# MCU.net
KiCad netlist of a schematic drawn in Altium Designer
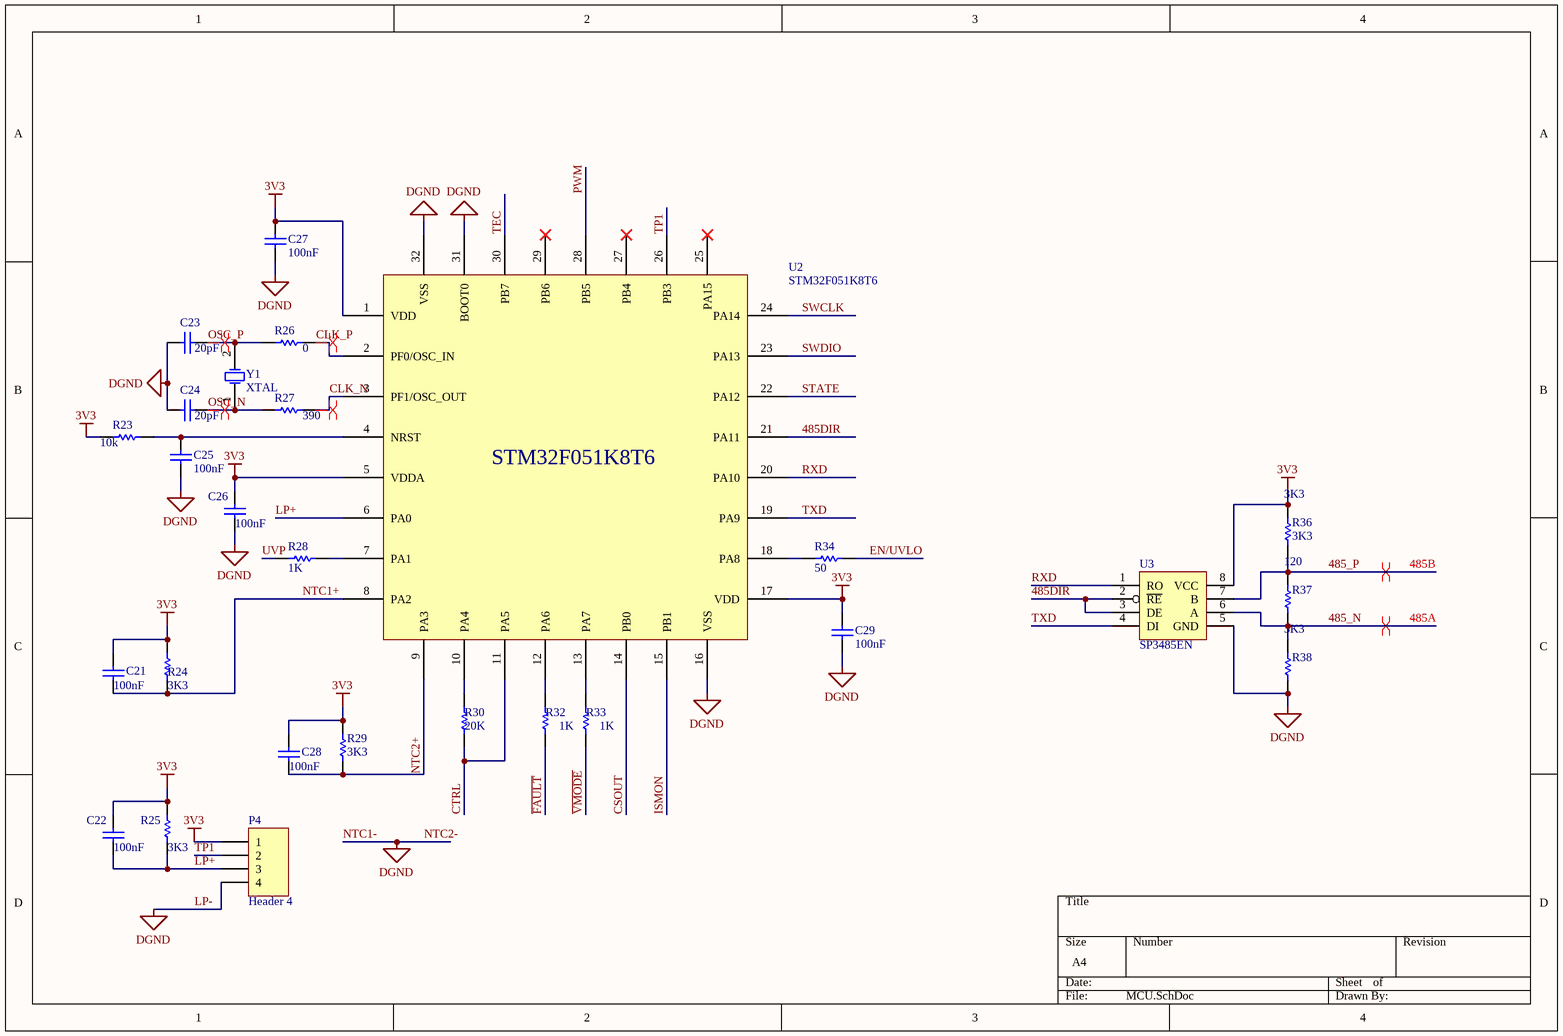
[diagram p0: MCU.SchDoc]

(export (version "E")
  (design (tool "Eeschema 10.0.6"))
  (components
    (comp (ref "C21")
      (value "100nF")
      (footprint "1608[0603]")
      (description "Capacitor")
      (fields (field (name "PUBLISHER") "Altium Limited"))
      (libsource (lib "Miscellaneous Devices") (part "Cap"))
    )
    (comp (ref "C22")
      (value "100nF")
      (footprint "1608[0603]")
      (description "Capacitor")
      (fields (field (name "PUBLISHER") "Altium Limited"))
      (libsource (lib "Miscellaneous Devices") (part "Cap"))
    )
    (comp (ref "C23")
      (value "20pF")
      (footprint "1608[0603]")
      (description "Capacitor")
      (fields (field (name "PUBLISHER") "Altium Limited"))
      (libsource (lib "Miscellaneous Devices") (part "Cap"))
    )
    (comp (ref "C24")
      (value "20pF")
      (footprint "1608[0603]")
      (description "Capacitor")
      (fields (field (name "PUBLISHER") "Altium Limited"))
      (libsource (lib "Miscellaneous Devices") (part "Cap"))
    )
    (comp (ref "C25")
      (value "100nF")
      (footprint "1608[0603]")
      (description "Capacitor")
      (fields (field (name "PUBLISHER") "Altium Limited"))
      (libsource (lib "Miscellaneous Devices") (part "Cap"))
    )
    (comp (ref "C26")
      (value "100nF")
      (footprint "1608[0603]")
      (description "Capacitor")
      (fields (field (name "PUBLISHER") "Altium Limited"))
      (libsource (lib "Miscellaneous Devices") (part "Cap"))
    )
    (comp (ref "C27")
      (value "100nF")
      (footprint "1608[0603]")
      (description "Capacitor")
      (fields (field (name "PUBLISHER") "Altium Limited"))
      (libsource (lib "Miscellaneous Devices") (part "Cap"))
    )
    (comp (ref "C28")
      (value "100nF")
      (footprint "1608[0603]")
      (description "Capacitor")
      (fields (field (name "PUBLISHER") "Altium Limited"))
      (libsource (lib "Miscellaneous Devices") (part "Cap"))
    )
    (comp (ref "C29")
      (value "100nF")
      (footprint "1608[0603]")
      (description "Capacitor")
      (fields (field (name "PUBLISHER") "Altium Limited"))
      (libsource (lib "Miscellaneous Devices") (part "Cap"))
    )
    (comp (ref "P4")
      (value "Header 4")
      (footprint "HDR1X4")
      (description "Header, 4-Pin")
      (fields (field (name "PUBLISHER") "Altium Limited"))
      (libsource (lib "Miscellaneous Connectors") (part "Header 4"))
    )
    (comp (ref "R23")
      (value "10k")
      (footprint "1608[0603]")
      (description "Resistor")
      (fields (field (name "PUBLISHER") "Altium Limited"))
      (libsource (lib "Miscellaneous Devices") (part "Res1"))
    )
    (comp (ref "R24")
      (value "3K3")
      (footprint "1608[0603]")
      (description "Resistor")
      (fields (field (name "PUBLISHER") "Altium Limited"))
      (libsource (lib "Miscellaneous Devices") (part "Res1"))
    )
    (comp (ref "R25")
      (value "3K3")
      (footprint "1608[0603]")
      (description "Resistor")
      (fields (field (name "PUBLISHER") "Altium Limited"))
      (libsource (lib "Miscellaneous Devices") (part "Res1"))
    )
    (comp (ref "R26")
      (value "0")
      (footprint "1608[0603]")
      (description "Resistor")
      (fields (field (name "PUBLISHER") "Altium Limited"))
      (libsource (lib "Miscellaneous Devices") (part "Res1"))
    )
    (comp (ref "R27")
      (value "390")
      (footprint "1608[0603]")
      (description "Resistor")
      (fields (field (name "PUBLISHER") "Altium Limited"))
      (libsource (lib "Miscellaneous Devices") (part "Res1"))
    )
    (comp (ref "R28")
      (value "1K")
      (footprint "1608[0603]")
      (description "Resistor")
      (fields (field (name "PUBLISHER") "Altium Limited"))
      (libsource (lib "Miscellaneous Devices") (part "Res1"))
    )
    (comp (ref "R29")
      (value "3K3")
      (footprint "1608[0603]")
      (description "Resistor")
      (fields (field (name "PUBLISHER") "Altium Limited"))
      (libsource (lib "Miscellaneous Devices") (part "Res1"))
    )
    (comp (ref "R30")
      (value "20K")
      (footprint "1608[0603]")
      (description "Resistor")
      (fields (field (name "PUBLISHER") "Altium Limited"))
      (libsource (lib "Miscellaneous Devices") (part "Res1"))
    )
    (comp (ref "R32")
      (value "1K")
      (footprint "1608[0603]")
      (description "Resistor")
      (fields (field (name "PUBLISHER") "Altium Limited"))
      (libsource (lib "Miscellaneous Devices") (part "Res1"))
    )
    (comp (ref "R33")
      (value "1K")
      (footprint "1608[0603]")
      (description "Resistor")
      (fields (field (name "PUBLISHER") "Altium Limited"))
      (libsource (lib "Miscellaneous Devices") (part "Res1"))
    )
    (comp (ref "R34")
      (value "50")
      (footprint "1608[0603]")
      (description "Resistor")
      (fields (field (name "PUBLISHER") "Altium Limited"))
      (libsource (lib "Miscellaneous Devices") (part "Res1"))
    )
    (comp (ref "R36")
      (value "3K3")
      (footprint "1608[0603]")
      (description "Resistor")
      (fields (field (name "ALTIUM_VALUE") "3K3") (field (name "PUBLISHER") "Altium Limited"))
      (libsource (lib "Miscellaneous Devices") (part "Res1"))
    )
    (comp (ref "R37")
      (value "120")
      (footprint "1608[0603]")
      (description "Resistor")
      (fields (field (name "PUBLISHER") "Altium Limited"))
      (libsource (lib "Miscellaneous Devices") (part "Res1"))
    )
    (comp (ref "R38")
      (value "3K3")
      (footprint "1608[0603]")
      (description "Resistor")
      (fields (field (name "PUBLISHER") "Altium Limited"))
      (libsource (lib "Miscellaneous Devices") (part "Res1"))
    )
    (comp (ref "U2")
      (value "STM32F051K8T6")
      (footprint "TQFP80P900X900X160-32N")
      (libsource (lib "Laser-LiuXin") (part "MCU_STM32F051K8T6"))
    )
    (comp (ref "U3")
      (value "SP3485EN")
      (footprint "Laser-LiuXin:SOIC127P600-8N")
      (description "Low-Power, Slew-Rate-Limited  RS-485/RS-422 Transceivers")
      (libsource (lib "Laser-LiuXin") (part "LGC_RS485"))
    )
    (comp (ref "Y1")
      (value "XTAL")
      (footprint "Laser-LiuXin:XTAL_SMT")
      (description "Crystal Oscillator")
      (fields (field (name "PUBLISHER") "Altium Limited"))
      (libsource (lib "Miscellaneous Devices") (part "XTAL"))
    )
  )
  (nets
    (net (code "1") (name "/485A") (class "Default")
      (node (ref "R37") (pin "1") (pinfunction "1_1") (pintype "passive"))
      (node (ref "R38") (pin "2") (pinfunction "2_2") (pintype "passive"))
      (node (ref "U3") (pin "6") (pinfunction "A_6") (pintype "passive"))
    )
    (net (code "2") (name "/485B") (class "Default")
      (node (ref "R36") (pin "1") (pinfunction "1_1") (pintype "passive"))
      (node (ref "R37") (pin "2") (pinfunction "2_2") (pintype "passive"))
      (node (ref "U3") (pin "7") (pinfunction "B_7") (pintype "passive"))
    )
    (net (code "3") (name "/485DIR") (class "Default")
      (node (ref "U2") (pin "21") (pinfunction "PA11_21") (pintype "passive"))
      (node (ref "U3") (pin "2") (pinfunction "~{RE}_2") (pintype "passive"))
      (node (ref "U3") (pin "3") (pinfunction "DE_3") (pintype "passive"))
    )
    (net (code "5") (name "/CLK_N") (class "Default")
      (node (ref "R27") (pin "2") (pinfunction "2_2") (pintype "passive"))
      (node (ref "U2") (pin "3") (pinfunction "PF1/OSC_OUT_3") (pintype "passive"))
    )
    (net (code "6") (name "/CLK_P") (class "Default")
      (node (ref "R26") (pin "2") (pinfunction "2_2") (pintype "passive"))
      (node (ref "U2") (pin "2") (pinfunction "PF0/OSC_IN_2") (pintype "passive"))
    )
    (net (code "7") (name "/CSOUT") (class "Default")
      (node (ref "U2") (pin "14") (pinfunction "PB0_14") (pintype "passive"))
    )
    (net (code "8") (name "/CTRL") (class "Default")
      (node (ref "R30") (pin "2") (pinfunction "2_2") (pintype "passive"))
      (node (ref "U2") (pin "11") (pinfunction "PA5_11") (pintype "passive"))
    )
    (net (code "9") (name "/EN{slash}UVLO") (class "Default")
      (node (ref "R34") (pin "2") (pinfunction "2_2") (pintype "passive"))
    )
    (net (code "10") (name "/ISMON") (class "Default")
      (node (ref "U2") (pin "15") (pinfunction "PB1_15") (pintype "passive"))
    )
    (net (code "11") (name "/LP+") (class "Default")
      (node (ref "C22") (pin "2") (pinfunction "2_2") (pintype "passive"))
      (node (ref "P4") (pin "3") (pinfunction "3_3") (pintype "passive"))
      (node (ref "R25") (pin "2") (pinfunction "2_2") (pintype "passive"))
      (node (ref "U2") (pin "6") (pinfunction "PA0_6") (pintype "passive"))
    )
    (net (code "12") (name "/NTC1+") (class "Default")
      (node (ref "C21") (pin "2") (pinfunction "2_2") (pintype "passive"))
      (node (ref "R24") (pin "2") (pinfunction "2_2") (pintype "passive"))
      (node (ref "U2") (pin "8") (pinfunction "PA2_8") (pintype "passive"))
    )
    (net (code "13") (name "/NTC2+") (class "Default")
      (node (ref "C28") (pin "2") (pinfunction "2_2") (pintype "passive"))
      (node (ref "R29") (pin "2") (pinfunction "2_2") (pintype "passive"))
      (node (ref "U2") (pin "9") (pinfunction "PA3_9") (pintype "passive"))
    )
    (net (code "14") (name "/OSC_N") (class "Default")
      (node (ref "C24") (pin "1") (pinfunction "1_1") (pintype "passive"))
      (node (ref "R27") (pin "1") (pinfunction "1_1") (pintype "passive"))
      (node (ref "Y1") (pin "1") (pinfunction "OSC1_1") (pintype "passive"))
    )
    (net (code "15") (name "/OSC_P") (class "Default")
      (node (ref "C23") (pin "1") (pinfunction "1_1") (pintype "passive"))
      (node (ref "R26") (pin "1") (pinfunction "1_1") (pintype "passive"))
      (node (ref "Y1") (pin "2") (pinfunction "OSC2_2") (pintype "passive"))
    )
    (net (code "16") (name "/PWM") (class "Default")
      (node (ref "U2") (pin "28") (pinfunction "PB5_28") (pintype "passive"))
    )
    (net (code "17") (name "/RXD") (class "Default")
      (node (ref "U2") (pin "20") (pinfunction "PA10_20") (pintype "passive"))
      (node (ref "U3") (pin "1") (pinfunction "RO_1") (pintype "passive"))
    )
    (net (code "18") (name "/STATE") (class "Default")
      (node (ref "U2") (pin "22") (pinfunction "PA12_22") (pintype "passive"))
    )
    (net (code "19") (name "/SWCLK") (class "Default")
      (node (ref "U2") (pin "24") (pinfunction "PA14_24") (pintype "passive"))
    )
    (net (code "20") (name "/SWDIO") (class "Default")
      (node (ref "U2") (pin "23") (pinfunction "PA13_23") (pintype "passive"))
    )
    (net (code "21") (name "/TEC") (class "Default")
      (node (ref "U2") (pin "30") (pinfunction "PB7_30") (pintype "passive"))
    )
    (net (code "22") (name "/TP1") (class "Default")
      (node (ref "P4") (pin "2") (pinfunction "2_2") (pintype "passive"))
      (node (ref "U2") (pin "26") (pinfunction "PB3_26") (pintype "passive"))
    )
    (net (code "23") (name "/TXD") (class "Default")
      (node (ref "U2") (pin "19") (pinfunction "PA9_19") (pintype "passive"))
      (node (ref "U3") (pin "4") (pinfunction "DI_4") (pintype "passive"))
    )
    (net (code "24") (name "/UVP") (class "Default")
      (node (ref "R28") (pin "1") (pinfunction "1_1") (pintype "passive"))
    )
    (net (code "25") (name "/~{FAULT}") (class "Default")
      (node (ref "R32") (pin "2") (pinfunction "2_2") (pintype "passive"))
    )
    (net (code "26") (name "/~{VMODE}") (class "Default")
      (node (ref "R33") (pin "2") (pinfunction "2_2") (pintype "passive"))
    )
    (net (code "27") (name "3V3") (class "Default")
      (node (ref "C21") (pin "1") (pinfunction "1_1") (pintype "passive"))
      (node (ref "C22") (pin "1") (pinfunction "1_1") (pintype "passive"))
      (node (ref "C26") (pin "1") (pinfunction "1_1") (pintype "passive"))
      (node (ref "C27") (pin "2") (pinfunction "2_2") (pintype "passive"))
      (node (ref "C28") (pin "1") (pinfunction "1_1") (pintype "passive"))
      (node (ref "C29") (pin "2") (pinfunction "2_2") (pintype "passive"))
      (node (ref "P4") (pin "1") (pinfunction "1_1") (pintype "passive"))
      (node (ref "R23") (pin "2") (pinfunction "2_2") (pintype "passive"))
      (node (ref "R24") (pin "1") (pinfunction "1_1") (pintype "passive"))
      (node (ref "R25") (pin "1") (pinfunction "1_1") (pintype "passive"))
      (node (ref "R29") (pin "1") (pinfunction "1_1") (pintype "passive"))
      (node (ref "R36") (pin "2") (pinfunction "2_2") (pintype "passive"))
      (node (ref "U2") (pin "1") (pinfunction "VDD_1") (pintype "passive"))
      (node (ref "U2") (pin "17") (pinfunction "VDD_17") (pintype "passive"))
      (node (ref "U2") (pin "5") (pinfunction "VDDA_5") (pintype "passive"))
      (node (ref "U3") (pin "8") (pinfunction "VCC_8") (pintype "passive"))
    )
    (net (code "28") (name "DGND") (class "Default")
      (node (ref "C23") (pin "2") (pinfunction "2_2") (pintype "passive"))
      (node (ref "C24") (pin "2") (pinfunction "2_2") (pintype "passive"))
      (node (ref "C25") (pin "1") (pinfunction "1_1") (pintype "passive"))
      (node (ref "C26") (pin "2") (pinfunction "2_2") (pintype "passive"))
      (node (ref "C27") (pin "1") (pinfunction "1_1") (pintype "passive"))
      (node (ref "C29") (pin "1") (pinfunction "1_1") (pintype "passive"))
      (node (ref "P4") (pin "4") (pinfunction "4_4") (pintype "passive"))
      (node (ref "R38") (pin "1") (pinfunction "1_1") (pintype "passive"))
      (node (ref "U2") (pin "16") (pinfunction "VSS_16") (pintype "passive"))
      (node (ref "U2") (pin "31") (pinfunction "BOOT0_31") (pintype "passive"))
      (node (ref "U2") (pin "32") (pinfunction "VSS_32") (pintype "passive"))
      (node (ref "U3") (pin "5") (pinfunction "GND_5") (pintype "passive"))
    )
    (net (code "29") (name "Net-(U2-NRST)") (class "Default")
      (node (ref "C25") (pin "2") (pinfunction "2_2") (pintype "passive"))
      (node (ref "R23") (pin "1") (pinfunction "1_1") (pintype "passive"))
      (node (ref "U2") (pin "4") (pinfunction "NRST_4") (pintype "passive"))
    )
    (net (code "30") (name "Net-(U2-PA1)") (class "Default")
      (node (ref "R28") (pin "2") (pinfunction "2_2") (pintype "passive"))
      (node (ref "U2") (pin "7") (pinfunction "PA1_7") (pintype "passive"))
    )
    (net (code "31") (name "Net-(U2-PA4)") (class "Default")
      (node (ref "R30") (pin "1") (pinfunction "1_1") (pintype "passive"))
      (node (ref "U2") (pin "10") (pinfunction "PA4_10") (pintype "passive"))
    )
    (net (code "32") (name "Net-(U2-PA6)") (class "Default")
      (node (ref "R32") (pin "1") (pinfunction "1_1") (pintype "passive"))
      (node (ref "U2") (pin "12") (pinfunction "PA6_12") (pintype "passive"))
    )
    (net (code "33") (name "Net-(U2-PA7)") (class "Default")
      (node (ref "R33") (pin "1") (pinfunction "1_1") (pintype "passive"))
      (node (ref "U2") (pin "13") (pinfunction "PA7_13") (pintype "passive"))
    )
    (net (code "34") (name "Net-(U2-PA8)") (class "Default")
      (node (ref "R34") (pin "1") (pinfunction "1_1") (pintype "passive"))
      (node (ref "U2") (pin "18") (pinfunction "PA8_18") (pintype "passive"))
    )
    (net (code "35") (name "unconnected-(U2-PA15-Pad25)") (class "Default")
      (node (ref "U2") (pin "25") (pinfunction "PA15_25") (pintype "passive+no_connect"))
    )
    (net (code "36") (name "unconnected-(U2-PB4-Pad27)") (class "Default")
      (node (ref "U2") (pin "27") (pinfunction "PB4_27") (pintype "passive+no_connect"))
    )
    (net (code "37") (name "unconnected-(U2-PB6-Pad29)") (class "Default")
      (node (ref "U2") (pin "29") (pinfunction "PB6_29") (pintype "passive+no_connect"))
    )
  )
)
